# M452r.net
KiCad netlist of a schematic drawn in EAGLE
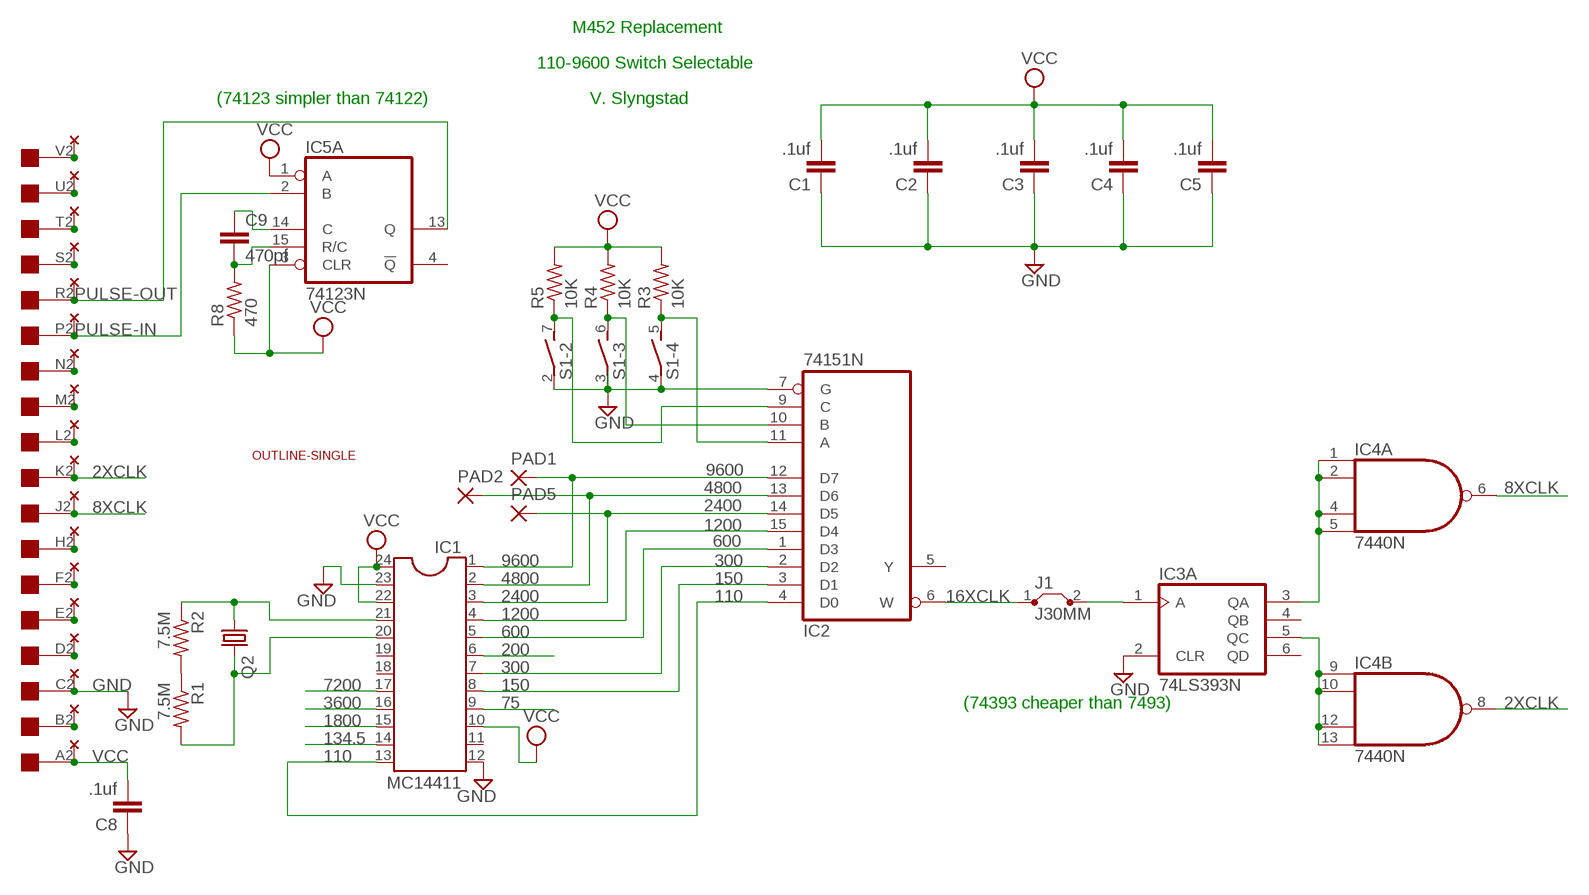
[diagram p0: schematic, sheet 1]

(export (version "E")
  (design (tool "Eeschema 10.0.6"))
  (components
    (comp (ref "C1")
      (value ".1uf")
      (footprint "eagle-import:C050-025X075")
      (libsource (lib "eagle-import") (part "C-EU050-025X075"))
    )
    (comp (ref "C2")
      (value ".1uf")
      (footprint "eagle-import:C050-025X075")
      (libsource (lib "eagle-import") (part "C-EU050-025X075"))
    )
    (comp (ref "C3")
      (value ".1uf")
      (footprint "eagle-import:C050-025X075")
      (libsource (lib "eagle-import") (part "C-EU050-025X075"))
    )
    (comp (ref "C4")
      (value ".1uf")
      (footprint "eagle-import:C050-025X075")
      (libsource (lib "eagle-import") (part "C-EU050-025X075"))
    )
    (comp (ref "C5")
      (value ".1uf")
      (footprint "eagle-import:C050-025X075")
      (libsource (lib "eagle-import") (part "C-EU050-025X075"))
    )
    (comp (ref "C8")
      (value ".1uf")
      (footprint "eagle-import:C050-025X075")
      (libsource (lib "eagle-import") (part "C-EU050-025X075"))
    )
    (comp (ref "C9")
      (value "470pf")
      (footprint "eagle-import:C050-025X075")
      (libsource (lib "eagle-import") (part "C-EU050-025X075"))
    )
    (comp (ref "IC1")
      (value "MC14411")
      (footprint "eagle-import:DIL24-6")
      (libsource (lib "eagle-import") (part "DIL24-6"))
    )
    (comp (ref "IC2")
      (value "74151N")
      (footprint "eagle-import:DIL16")
      (libsource (lib "eagle-import") (part "74151N"))
    )
    (comp (ref "IC3")
      (value "74LS393N")
      (footprint "eagle-import:DIL14")
      (libsource (lib "eagle-import") (part "74393NLS"))
    )
    (comp (ref "IC4")
      (value "7440N")
      (footprint "eagle-import:DIL14")
      (libsource (lib "eagle-import") (part "7420NS"))
    )
    (comp (ref "IC5")
      (value "74123N")
      (footprint "eagle-import:DIL16")
      (libsource (lib "eagle-import") (part "74123N"))
    )
    (comp (ref "J1")
      (value "J30MM")
      (footprint "eagle-import:30")
      (libsource (lib "eagle-import") (part "J30MM"))
    )
    (comp (ref "PAD1")
      (value "1,6/0,8")
      (footprint "eagle-import:1,6_0,8")
      (libsource (lib "eagle-import") (part "1,6/0,8"))
    )
    (comp (ref "PAD2")
      (value "1,6/0,8")
      (footprint "eagle-import:1,6_0,8")
      (libsource (lib "eagle-import") (part "1,6/0,8"))
    )
    (comp (ref "PAD5")
      (value "1,6/0,8")
      (footprint "eagle-import:1,6_0,8")
      (libsource (lib "eagle-import") (part "1,6/0,8"))
    )
    (comp (ref "Q2")
      (value "CRYSTALHC49U-H")
      (footprint "eagle-import:HC49U-H")
      (libsource (lib "eagle-import") (part "CRYSTALHC49U-H"))
    )
    (comp (ref "R1")
      (value "7.5M")
      (footprint "eagle-import:0204_7")
      (libsource (lib "eagle-import") (part "R-US_0204/7"))
    )
    (comp (ref "R2")
      (value "7.5M")
      (footprint "eagle-import:0204_7")
      (libsource (lib "eagle-import") (part "R-US_0204/7"))
    )
    (comp (ref "R3")
      (value "10K")
      (footprint "eagle-import:0204_7")
      (libsource (lib "eagle-import") (part "R-US_0204/7"))
    )
    (comp (ref "R4")
      (value "10K")
      (footprint "eagle-import:0204_7")
      (libsource (lib "eagle-import") (part "R-US_0204/7"))
    )
    (comp (ref "R5")
      (value "10K")
      (footprint "eagle-import:0204_7")
      (libsource (lib "eagle-import") (part "R-US_0204/7"))
    )
    (comp (ref "R8")
      (value "470")
      (footprint "eagle-import:0204_7")
      (libsource (lib "eagle-import") (part "R-US_0204/7"))
    )
    (comp (ref "S1")
      (value "DIP04S")
      (footprint "eagle-import:DIP04S")
      (libsource (lib "eagle-import") (part "DIP04S"))
    )
    (comp (ref "U$2")
      (value "EDGE-1")
      (footprint "eagle-import:EDGE-CON1")
      (libsource (lib "eagle-import") (part "EDGE-1"))
    )
    (comp (ref "U$3")
      (value "THRU-HOLE1")
      (footprint "eagle-import:THRU-HOLE1")
      (libsource (lib "eagle-import") (part "THRU-HOLE1"))
    )
    (comp (ref "U$4")
      (value "OUTLINE-SINGLE")
      (footprint "eagle-import:SINGLE")
      (libsource (lib "eagle-import") (part "OUTLINE-SINGLE"))
    )
  )
  (nets
    (net (code "1") (name "/2XCLK") (class "Default")
      (node (ref "IC4") (pin "8") (pinfunction "O_8") (pintype "output"))
      (node (ref "U$2") (pin "K2") (pinfunction "1_K2") (pintype "bidirectional"))
      (node (ref "U$3") (pin "K2") (pinfunction "P$1_K2") (pintype "passive"))
    )
    (net (code "2") (name "/8XCLK") (class "Default")
      (node (ref "IC4") (pin "6") (pinfunction "O_6") (pintype "output"))
      (node (ref "U$2") (pin "J2") (pinfunction "1_J2") (pintype "bidirectional"))
      (node (ref "U$3") (pin "J2") (pinfunction "P$1_J2") (pintype "passive"))
    )
    (net (code "3") (name "/16XCLK") (class "Default")
      (node (ref "IC2") (pin "6") (pinfunction "W_6") (pintype "output"))
      (node (ref "J1") (pin "1") (pinfunction "1_1") (pintype "passive"))
    )
    (net (code "4") (name "/75") (class "Default")
      (node (ref "IC1") (pin "9") (pinfunction "9_9") (pintype "passive"))
    )
    (net (code "5") (name "/110") (class "Default")
      (node (ref "IC1") (pin "13") (pinfunction "13_13") (pintype "passive"))
      (node (ref "IC2") (pin "4") (pinfunction "D0_4") (pintype "input"))
    )
    (net (code "6") (name "/134.5") (class "Default")
      (node (ref "IC1") (pin "14") (pinfunction "14_14") (pintype "passive"))
    )
    (net (code "7") (name "/150") (class "Default")
      (node (ref "IC1") (pin "8") (pinfunction "8_8") (pintype "passive"))
      (node (ref "IC2") (pin "3") (pinfunction "D1_3") (pintype "input"))
    )
    (net (code "8") (name "/200") (class "Default")
      (node (ref "IC1") (pin "6") (pinfunction "6_6") (pintype "passive"))
    )
    (net (code "9") (name "/300") (class "Default")
      (node (ref "IC1") (pin "7") (pinfunction "7_7") (pintype "passive"))
      (node (ref "IC2") (pin "2") (pinfunction "D2_2") (pintype "input"))
    )
    (net (code "10") (name "/600") (class "Default")
      (node (ref "IC1") (pin "5") (pinfunction "5_5") (pintype "passive"))
      (node (ref "IC2") (pin "1") (pinfunction "D3_1") (pintype "input"))
    )
    (net (code "11") (name "/1200") (class "Default")
      (node (ref "IC1") (pin "4") (pinfunction "4_4") (pintype "passive"))
      (node (ref "IC2") (pin "15") (pinfunction "D4_15") (pintype "input"))
    )
    (net (code "12") (name "/1800") (class "Default")
      (node (ref "IC1") (pin "15") (pinfunction "15_15") (pintype "passive"))
    )
    (net (code "13") (name "/2400") (class "Default")
      (node (ref "IC1") (pin "3") (pinfunction "3_3") (pintype "passive"))
      (node (ref "IC2") (pin "14") (pinfunction "D5_14") (pintype "input"))
      (node (ref "PAD5") (pin "1") (pinfunction "P_1") (pintype "passive"))
    )
    (net (code "14") (name "/3600") (class "Default")
      (node (ref "IC1") (pin "16") (pinfunction "16_16") (pintype "passive"))
    )
    (net (code "15") (name "/4800") (class "Default")
      (node (ref "IC1") (pin "2") (pinfunction "2_2") (pintype "passive"))
      (node (ref "IC2") (pin "13") (pinfunction "D6_13") (pintype "input"))
      (node (ref "PAD2") (pin "1") (pinfunction "P_1") (pintype "passive"))
    )
    (net (code "16") (name "/7200") (class "Default")
      (node (ref "IC1") (pin "17") (pinfunction "17_17") (pintype "passive"))
    )
    (net (code "17") (name "/9600") (class "Default")
      (node (ref "IC1") (pin "1") (pinfunction "1_1") (pintype "passive"))
      (node (ref "IC2") (pin "12") (pinfunction "D7_12") (pintype "input"))
      (node (ref "PAD1") (pin "1") (pinfunction "P_1") (pintype "passive"))
    )
    (net (code "18") (name "/PULSE-IN") (class "Default")
      (node (ref "IC5") (pin "2") (pinfunction "B_2") (pintype "input"))
      (node (ref "U$2") (pin "P2") (pinfunction "1_P2") (pintype "bidirectional"))
      (node (ref "U$3") (pin "P2") (pinfunction "P$1_P2") (pintype "passive"))
    )
    (net (code "19") (name "/PULSE-OUT") (class "Default")
      (node (ref "IC5") (pin "13") (pinfunction "Q_13") (pintype "output"))
      (node (ref "U$2") (pin "R2") (pinfunction "1_R2") (pintype "bidirectional"))
      (node (ref "U$3") (pin "R2") (pinfunction "P$1_R2") (pintype "passive"))
    )
    (net (code "20") (name "GND") (class "Default")
      (node (ref "C1") (pin "1") (pinfunction "1_1") (pintype "passive"))
      (node (ref "C2") (pin "1") (pinfunction "1_1") (pintype "passive"))
      (node (ref "C3") (pin "1") (pinfunction "1_1") (pintype "passive"))
      (node (ref "C4") (pin "1") (pinfunction "1_1") (pintype "passive"))
      (node (ref "C5") (pin "1") (pinfunction "1_1") (pintype "passive"))
      (node (ref "C8") (pin "1") (pinfunction "1_1") (pintype "passive"))
      (node (ref "IC1") (pin "12") (pinfunction "12_12") (pintype "passive"))
      (node (ref "IC1") (pin "23") (pinfunction "23_23") (pintype "passive"))
      (node (ref "IC2") (pin "7") (pinfunction "G_7") (pintype "input"))
      (node (ref "IC3") (pin "2") (pinfunction "CLR_2") (pintype "input"))
      (node (ref "S1") (pin "2") (pinfunction "1_2") (pintype "passive"))
      (node (ref "S1") (pin "3") (pinfunction "1_3") (pintype "passive"))
      (node (ref "S1") (pin "4") (pinfunction "1_4") (pintype "passive"))
      (node (ref "U$2") (pin "C2") (pinfunction "1_C2") (pintype "bidirectional"))
      (node (ref "U$3") (pin "C2") (pinfunction "P$1_C2") (pintype "passive"))
    )
    (net (code "21") (name "Net-(IC1-Pad20)") (class "Default")
      (node (ref "IC1") (pin "20") (pinfunction "20_20") (pintype "passive"))
      (node (ref "Q2") (pin "2") (pinfunction "2_2") (pintype "passive"))
      (node (ref "R1") (pin "2") (pinfunction "2_2") (pintype "passive"))
    )
    (net (code "22") (name "Net-(IC1-Pad21)") (class "Default")
      (node (ref "IC1") (pin "21") (pinfunction "21_21") (pintype "passive"))
      (node (ref "Q2") (pin "1") (pinfunction "1_1") (pintype "passive"))
      (node (ref "R2") (pin "1") (pinfunction "1_1") (pintype "passive"))
    )
    (net (code "23") (name "Net-(IC2A-A)") (class "Default")
      (node (ref "IC2") (pin "11") (pinfunction "A_11") (pintype "input"))
      (node (ref "R3") (pin "1") (pinfunction "1_1") (pintype "passive"))
      (node (ref "S1") (pin "5") (pinfunction "2_5") (pintype "passive"))
    )
    (net (code "24") (name "Net-(IC2A-B)") (class "Default")
      (node (ref "IC2") (pin "10") (pinfunction "B_10") (pintype "input"))
      (node (ref "R4") (pin "1") (pinfunction "1_1") (pintype "passive"))
      (node (ref "S1") (pin "6") (pinfunction "2_6") (pintype "passive"))
    )
    (net (code "25") (name "Net-(IC2A-C)") (class "Default")
      (node (ref "IC2") (pin "9") (pinfunction "C_9") (pintype "input"))
      (node (ref "R5") (pin "1") (pinfunction "1_1") (pintype "passive"))
      (node (ref "S1") (pin "7") (pinfunction "2_7") (pintype "passive"))
    )
    (net (code "26") (name "Net-(IC3A-A)") (class "Default")
      (node (ref "IC3") (pin "1") (pinfunction "A_1") (pintype "input"))
      (node (ref "J1") (pin "2") (pinfunction "2_2") (pintype "passive"))
    )
    (net (code "27") (name "Net-(IC3A-QA)") (class "Default")
      (node (ref "IC3") (pin "3") (pinfunction "QA_3") (pintype "output"))
      (node (ref "IC4") (pin "1") (pinfunction "I0_1") (pintype "input"))
      (node (ref "IC4") (pin "2") (pinfunction "I1_2") (pintype "input"))
      (node (ref "IC4") (pin "4") (pinfunction "I2_4") (pintype "input"))
      (node (ref "IC4") (pin "5") (pinfunction "I3_5") (pintype "input"))
    )
    (net (code "28") (name "Net-(IC3A-QC)") (class "Default")
      (node (ref "IC3") (pin "5") (pinfunction "QC_5") (pintype "output"))
      (node (ref "IC4") (pin "10") (pinfunction "I1_10") (pintype "input"))
      (node (ref "IC4") (pin "12") (pinfunction "I2_12") (pintype "input"))
      (node (ref "IC4") (pin "13") (pinfunction "I3_13") (pintype "input"))
      (node (ref "IC4") (pin "9") (pinfunction "I0_9") (pintype "input"))
    )
    (net (code "29") (name "Net-(IC5A-C)") (class "Default")
      (node (ref "C9") (pin "1") (pinfunction "1_1") (pintype "passive"))
      (node (ref "IC5") (pin "14") (pinfunction "C_14") (pintype "input"))
    )
    (net (code "30") (name "Net-(IC5A-R{slash}C)") (class "Default")
      (node (ref "C9") (pin "2") (pinfunction "2_2") (pintype "passive"))
      (node (ref "IC5") (pin "15") (pinfunction "R/C_15") (pintype "input"))
      (node (ref "R8") (pin "2") (pinfunction "2_2") (pintype "passive"))
    )
    (net (code "31") (name "Net-(R1-Pad1)") (class "Default")
      (node (ref "R1") (pin "1") (pinfunction "1_1") (pintype "passive"))
      (node (ref "R2") (pin "2") (pinfunction "2_2") (pintype "passive"))
    )
    (net (code "32") (name "Net-(U$2B-1)") (class "Default")
      (node (ref "U$2") (pin "B2") (pinfunction "1_B2") (pintype "bidirectional"))
      (node (ref "U$3") (pin "B2") (pinfunction "P$1_B2") (pintype "passive"))
    )
    (net (code "33") (name "Net-(U$2D-1)") (class "Default")
      (node (ref "U$2") (pin "D2") (pinfunction "1_D2") (pintype "bidirectional"))
      (node (ref "U$3") (pin "D2") (pinfunction "P$1_D2") (pintype "passive"))
    )
    (net (code "34") (name "Net-(U$2E-1)") (class "Default")
      (node (ref "U$2") (pin "E2") (pinfunction "1_E2") (pintype "bidirectional"))
      (node (ref "U$3") (pin "E2") (pinfunction "P$1_E2") (pintype "passive"))
    )
    (net (code "35") (name "Net-(U$2F-1)") (class "Default")
      (node (ref "U$2") (pin "F2") (pinfunction "1_F2") (pintype "bidirectional"))
      (node (ref "U$3") (pin "F2") (pinfunction "P$1_F2") (pintype "passive"))
    )
    (net (code "36") (name "Net-(U$2G-1)") (class "Default")
      (node (ref "U$2") (pin "H2") (pinfunction "1_H2") (pintype "bidirectional"))
      (node (ref "U$3") (pin "H2") (pinfunction "P$1_H2") (pintype "passive"))
    )
    (net (code "37") (name "Net-(U$2J-1)") (class "Default")
      (node (ref "U$2") (pin "L2") (pinfunction "1_L2") (pintype "bidirectional"))
      (node (ref "U$3") (pin "L2") (pinfunction "P$1_L2") (pintype "passive"))
    )
    (net (code "38") (name "Net-(U$2K-1)") (class "Default")
      (node (ref "U$2") (pin "M2") (pinfunction "1_M2") (pintype "bidirectional"))
      (node (ref "U$3") (pin "M2") (pinfunction "P$1_M2") (pintype "passive"))
    )
    (net (code "39") (name "Net-(U$2L-1)") (class "Default")
      (node (ref "U$2") (pin "N2") (pinfunction "1_N2") (pintype "bidirectional"))
      (node (ref "U$3") (pin "N2") (pinfunction "P$1_N2") (pintype "passive"))
    )
    (net (code "40") (name "Net-(U$2O-1)") (class "Default")
      (node (ref "U$2") (pin "S2") (pinfunction "1_S2") (pintype "bidirectional"))
      (node (ref "U$3") (pin "S2") (pinfunction "P$1_S2") (pintype "passive"))
    )
    (net (code "41") (name "Net-(U$2P-1)") (class "Default")
      (node (ref "U$2") (pin "T2") (pinfunction "1_T2") (pintype "bidirectional"))
      (node (ref "U$3") (pin "T2") (pinfunction "P$1_T2") (pintype "passive"))
    )
    (net (code "42") (name "Net-(U$2Q-1)") (class "Default")
      (node (ref "U$2") (pin "U2") (pinfunction "1_U2") (pintype "bidirectional"))
      (node (ref "U$3") (pin "U2") (pinfunction "P$1_U2") (pintype "passive"))
    )
    (net (code "43") (name "Net-(U$2R-1)") (class "Default")
      (node (ref "U$2") (pin "V2") (pinfunction "1_V2") (pintype "bidirectional"))
      (node (ref "U$3") (pin "V2") (pinfunction "P$1_V2") (pintype "passive"))
    )
    (net (code "44") (name "VCC") (class "Default")
      (node (ref "C1") (pin "2") (pinfunction "2_2") (pintype "passive"))
      (node (ref "C2") (pin "2") (pinfunction "2_2") (pintype "passive"))
      (node (ref "C3") (pin "2") (pinfunction "2_2") (pintype "passive"))
      (node (ref "C4") (pin "2") (pinfunction "2_2") (pintype "passive"))
      (node (ref "C5") (pin "2") (pinfunction "2_2") (pintype "passive"))
      (node (ref "C8") (pin "2") (pinfunction "2_2") (pintype "passive"))
      (node (ref "IC1") (pin "10") (pinfunction "10_10") (pintype "passive"))
      (node (ref "IC1") (pin "22") (pinfunction "22_22") (pintype "passive"))
      (node (ref "IC1") (pin "24") (pinfunction "24_24") (pintype "passive"))
      (node (ref "IC5") (pin "1") (pinfunction "A_1") (pintype "input"))
      (node (ref "IC5") (pin "3") (pinfunction "CLR_3") (pintype "input"))
      (node (ref "R3") (pin "2") (pinfunction "2_2") (pintype "passive"))
      (node (ref "R4") (pin "2") (pinfunction "2_2") (pintype "passive"))
      (node (ref "R5") (pin "2") (pinfunction "2_2") (pintype "passive"))
      (node (ref "R8") (pin "1") (pinfunction "1_1") (pintype "passive"))
      (node (ref "U$2") (pin "A2") (pinfunction "1_A2") (pintype "bidirectional"))
      (node (ref "U$3") (pin "A2") (pinfunction "P$1_A2") (pintype "passive"))
    )
    (net (code "45") (name "unconnected-(IC1-Pad11)") (class "Default")
      (node (ref "IC1") (pin "11") (pinfunction "11_11") (pintype "passive"))
    )
    (net (code "46") (name "unconnected-(IC1-Pad18)") (class "Default")
      (node (ref "IC1") (pin "18") (pinfunction "18_18") (pintype "passive"))
    )
    (net (code "47") (name "unconnected-(IC1-Pad19)") (class "Default")
      (node (ref "IC1") (pin "19") (pinfunction "19_19") (pintype "passive"))
    )
    (net (code "48") (name "unconnected-(IC2A-Y-Pad5)") (class "Default")
      (node (ref "IC2") (pin "5") (pinfunction "Y_5") (pintype "output"))
    )
    (net (code "49") (name "unconnected-(IC3A-QB-Pad4)") (class "Default")
      (node (ref "IC3") (pin "4") (pinfunction "QB_4") (pintype "output"))
    )
    (net (code "50") (name "unconnected-(IC3A-QD-Pad6)") (class "Default")
      (node (ref "IC3") (pin "6") (pinfunction "QD_6") (pintype "output"))
    )
    (net (code "51") (name "unconnected-(IC5A-~{Q}-Pad4)") (class "Default")
      (node (ref "IC5") (pin "4") (pinfunction "~{Q}_4") (pintype "output"))
    )
  )
)
